# PCB_battery.net
KiCad netlist of a schematic drawn in EAGLE
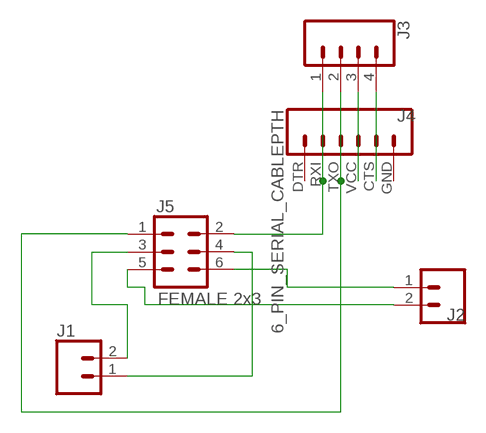
[diagram p0: schematic, sheet 1]

(export (version "E")
  (design (tool "Eeschema 10.0.6"))
  (components
    (comp (ref "J1")
      (value "CONN_02")
      (footprint "eagle-import:1X02")
      (libsource (lib "eagle-import") (part "CONN_02"))
    )
    (comp (ref "J2")
      (value "CONN_02")
      (footprint "eagle-import:1X02")
      (libsource (lib "eagle-import") (part "CONN_02"))
    )
    (comp (ref "J3")
      (value "CONN_04LOCK")
      (footprint "eagle-import:1X04_LOCK")
      (libsource (lib "eagle-import") (part "CONN_04LOCK"))
    )
    (comp (ref "J4")
      (value "6_PIN_SERIAL_CABLEPTH")
      (footprint "eagle-import:FTDI_BASIC")
      (libsource (lib "eagle-import") (part "6_PIN_SERIAL_CABLEPTH"))
    )
    (comp (ref "J5")
      (value "FEMALE 2x3")
      (footprint "eagle-import:2X3")
      (libsource (lib "eagle-import") (part "CONN_03X2FEMALE"))
    )
  )
  (nets
    (net (code "1") (name "Net-(J1-Pad1)") (class "Default")
      (node (ref "J1") (pin "1") (pinfunction "1_1") (pintype "passive"))
      (node (ref "J5") (pin "4") (pinfunction "4_4") (pintype "bidirectional"))
    )
    (net (code "2") (name "Net-(J1-Pad2)") (class "Default")
      (node (ref "J1") (pin "2") (pinfunction "2_2") (pintype "passive"))
      (node (ref "J5") (pin "3") (pinfunction "3_3") (pintype "bidirectional"))
    )
    (net (code "3") (name "Net-(J2-Pad1)") (class "Default")
      (node (ref "J2") (pin "1") (pinfunction "1_1") (pintype "passive"))
      (node (ref "J5") (pin "6") (pinfunction "6_6") (pintype "bidirectional"))
    )
    (net (code "4") (name "Net-(J2-Pad2)") (class "Default")
      (node (ref "J2") (pin "2") (pinfunction "2_2") (pintype "passive"))
      (node (ref "J5") (pin "5") (pinfunction "5_5") (pintype "bidirectional"))
    )
    (net (code "5") (name "Net-(J4-2)") (class "Default")
      (node (ref "J3") (pin "1") (pinfunction "1_1") (pintype "passive"))
      (node (ref "J4") (pin "RXI") (pinfunction "2_RXI") (pintype "passive"))
      (node (ref "J5") (pin "2") (pinfunction "2_2") (pintype "bidirectional"))
    )
    (net (code "6") (name "Net-(J4-3)") (class "Default")
      (node (ref "J3") (pin "2") (pinfunction "2_2") (pintype "passive"))
      (node (ref "J4") (pin "TXO") (pinfunction "3_TXO") (pintype "passive"))
      (node (ref "J5") (pin "1") (pinfunction "1_1") (pintype "bidirectional"))
    )
    (net (code "7") (name "Net-(J4-4)") (class "Default")
      (node (ref "J3") (pin "3") (pinfunction "3_3") (pintype "passive"))
      (node (ref "J4") (pin "VCC") (pinfunction "4_VCC") (pintype "passive"))
    )
    (net (code "8") (name "Net-(J4-5)") (class "Default")
      (node (ref "J3") (pin "4") (pinfunction "4_4") (pintype "passive"))
      (node (ref "J4") (pin "CTS") (pinfunction "5_CTS") (pintype "passive"))
    )
    (net (code "9") (name "unconnected-(J4-1-PadDTR)") (class "Default")
      (node (ref "J4") (pin "DTR") (pinfunction "1_DTR") (pintype "passive"))
    )
    (net (code "10") (name "unconnected-(J4-6-PadGND)") (class "Default")
      (node (ref "J4") (pin "GND") (pinfunction "6_GND") (pintype "passive"))
    )
  )
)
